# STM32L412CBU6.net
KiCad netlist of a schematic drawn in Altium Designer
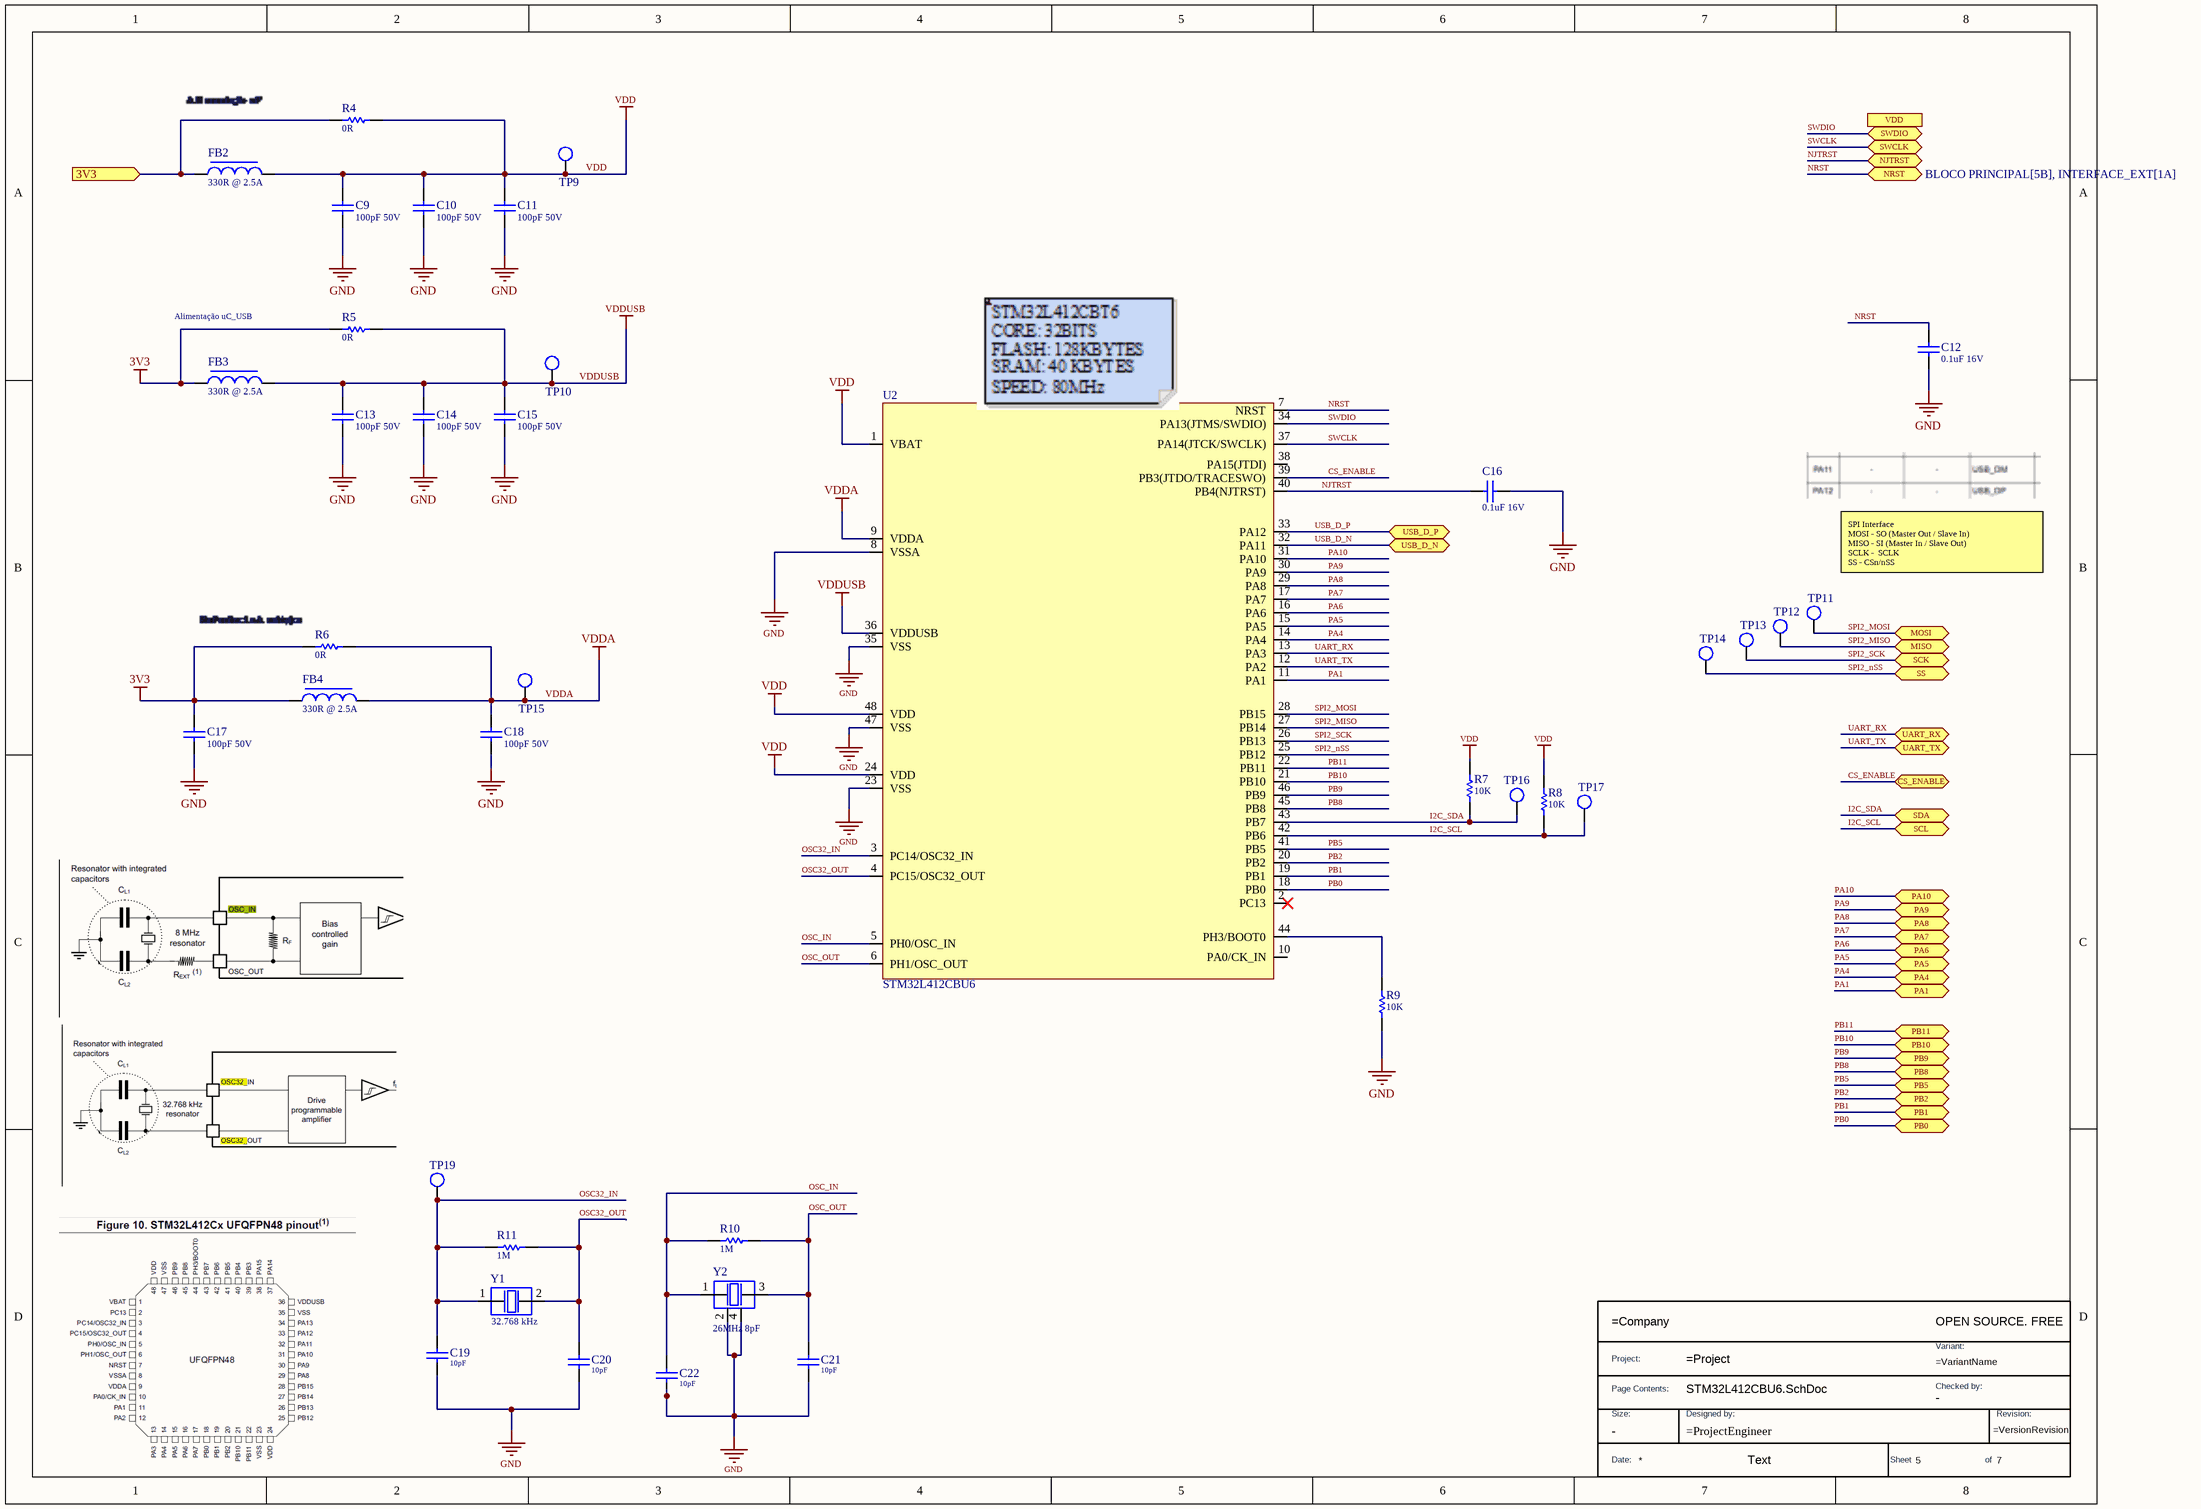
[diagram p0: STM32L412CBU6.SchDoc]

(export (version "E")
  (design (tool "Eeschema 10.0.6"))
  (components
    (comp (ref "C9")
      (value "CC0805JRNPO9BN101")
      (footprint "CAP_0805")
      (description "CAP CER 100PF 50V C0G/NPO 0805")
      (fields (field (name "MANUFACTURER") "YAGEO") (field (name "VALOR") "100pF 50V"))
      (libsource (lib "OBDH_Ed02") (part "CC0805JRNPO9BN101"))
    )
    (comp (ref "C10")
      (value "CC0805JRNPO9BN101")
      (footprint "CAP_0805")
      (description "CAP CER 100PF 50V C0G/NPO 0805")
      (fields (field (name "MANUFACTURER") "YAGEO") (field (name "VALOR") "100pF 50V"))
      (libsource (lib "OBDH_Ed02") (part "CC0805JRNPO9BN101"))
    )
    (comp (ref "C11")
      (value "CC0805JRNPO9BN101")
      (footprint "CAP_0805")
      (description "CAP CER 100PF 50V C0G/NPO 0805")
      (fields (field (name "MANUFACTURER") "YAGEO") (field (name "VALOR") "100pF 50V"))
      (libsource (lib "OBDH_Ed02") (part "CC0805JRNPO9BN101"))
    )
    (comp (ref "C12")
      (value "CL05B104KO5NNNC")
      (footprint "CAP_0805")
      (description "CAP CER 0.1UF 16V X5R 0805")
      (fields (field (name "MANUFACTURER") "Samsung Electro-Mechanics") (field (name "VALOR") "0.1uF 16V"))
      (libsource (lib "OBDH_Ed02") (part "CL05B104KO5NNNC"))
    )
    (comp (ref "C13")
      (value "CC0805JRNPO9BN101")
      (footprint "CAP_0805")
      (description "CAP CER 100PF 50V C0G/NPO 0805")
      (fields (field (name "MANUFACTURER") "YAGEO") (field (name "VALOR") "100pF 50V"))
      (libsource (lib "OBDH_Ed02") (part "CC0805JRNPO9BN101"))
    )
    (comp (ref "C14")
      (value "CC0805JRNPO9BN101")
      (footprint "CAP_0805")
      (description "CAP CER 100PF 50V C0G/NPO 0805")
      (fields (field (name "MANUFACTURER") "YAGEO") (field (name "VALOR") "100pF 50V"))
      (libsource (lib "OBDH_Ed02") (part "CC0805JRNPO9BN101"))
    )
    (comp (ref "C15")
      (value "CC0805JRNPO9BN101")
      (footprint "CAP_0805")
      (description "CAP CER 100PF 50V C0G/NPO 0805")
      (fields (field (name "MANUFACTURER") "YAGEO") (field (name "VALOR") "100pF 50V"))
      (libsource (lib "OBDH_Ed02") (part "CC0805JRNPO9BN101"))
    )
    (comp (ref "C16")
      (value "CL05B104KO5NNNC")
      (footprint "CAP_0805")
      (description "CAP CER 0.1UF 16V X5R 0805")
      (fields (field (name "MANUFACTURER") "Samsung Electro-Mechanics") (field (name "VALOR") "0.1uF 16V"))
      (libsource (lib "OBDH_Ed02") (part "CL05B104KO5NNNC"))
    )
    (comp (ref "C17")
      (value "CC0805JRNPO9BN101")
      (footprint "CAP_0805")
      (description "CAP CER 100PF 50V C0G/NPO 0805")
      (fields (field (name "MANUFACTURER") "YAGEO") (field (name "VALOR") "100pF 50V"))
      (libsource (lib "OBDH_Ed02") (part "CC0805JRNPO9BN101"))
    )
    (comp (ref "C18")
      (value "CC0805JRNPO9BN101")
      (footprint "CAP_0805")
      (description "CAP CER 100PF 50V C0G/NPO 0805")
      (fields (field (name "MANUFACTURER") "YAGEO") (field (name "VALOR") "100pF 50V"))
      (libsource (lib "OBDH_Ed02") (part "CC0805JRNPO9BN101"))
    )
    (comp (ref "C19")
      (value "GRM1555C1H100FA01D")
      (footprint "CAP 0402")
      (description "CAP CER 10PF 50V C0G/NP0 0402")
      (fields (field (name "MANUFACTURER") "Murata Electronics") (field (name "VALOR") "10pF"))
      (libsource (lib "OBDH_Ed02") (part "GRM1555C1H100FA01D"))
    )
    (comp (ref "C20")
      (value "GRM1555C1H100FA01D")
      (footprint "CAP 0402")
      (description "CAP CER 10PF 50V C0G/NP0 0402")
      (fields (field (name "MANUFACTURER") "Murata Electronics") (field (name "VALOR") "10pF"))
      (libsource (lib "OBDH_Ed02") (part "GRM1555C1H100FA01D"))
    )
    (comp (ref "C21")
      (value "GRM1555C1H100FA01D")
      (footprint "CAP 0402")
      (description "CAP CER 10PF 50V C0G/NP0 0402")
      (fields (field (name "MANUFACTURER") "Murata Electronics") (field (name "VALOR") "10pF"))
      (libsource (lib "OBDH_Ed02") (part "GRM1555C1H100FA01D"))
    )
    (comp (ref "C22")
      (value "GRM1555C1H100FA01D")
      (footprint "CAP 0402")
      (description "CAP CER 10PF 50V C0G/NP0 0402")
      (fields (field (name "MANUFACTURER") "Murata Electronics") (field (name "VALOR") "10pF"))
      (libsource (lib "OBDH_Ed02") (part "GRM1555C1H100FA01D"))
    )
    (comp (ref "FB2")
      (value "MPZ2012S331AT000")
      (footprint "IND_0805")
      (description "FERRITE BEAD 330 OHM 0805 1LN")
      (fields (field (name "MANUFACTURER") "TDK Corporation") (field (name "VALOR") "330R @ 2.5A"))
      (libsource (lib "OBDH_Ed02") (part "MPZ2012S331AT000"))
    )
    (comp (ref "FB3")
      (value "MPZ2012S331AT000")
      (footprint "IND_0805")
      (description "FERRITE BEAD 330 OHM 0805 1LN")
      (fields (field (name "MANUFACTURER") "TDK Corporation") (field (name "VALOR") "330R @ 2.5A"))
      (libsource (lib "OBDH_Ed02") (part "MPZ2012S331AT000"))
    )
    (comp (ref "FB4")
      (value "MPZ2012S331AT000")
      (footprint "IND_0805")
      (description "FERRITE BEAD 330 OHM 0805 1LN")
      (fields (field (name "MANUFACTURER") "TDK Corporation") (field (name "VALOR") "330R @ 2.5A"))
      (libsource (lib "OBDH_Ed02") (part "MPZ2012S331AT000"))
    )
    (comp (ref "R4")
      (value "RC0805JR-070RL")
      (footprint "RES_0805")
      (description "RES 0 OHM JUMPER 1/8W 0805")
      (fields (field (name "MANUFACTURER") "YAGEO") (field (name "VALOR") "0R"))
      (libsource (lib "OBDH_Ed02") (part "RC0805JR-070RL"))
    )
    (comp (ref "R5")
      (value "RC0805JR-070RL")
      (footprint "RES_0805")
      (description "RES 0 OHM JUMPER 1/8W 0805")
      (fields (field (name "MANUFACTURER") "YAGEO") (field (name "VALOR") "0R"))
      (libsource (lib "OBDH_Ed02") (part "RC0805JR-070RL"))
    )
    (comp (ref "R6")
      (value "RC0805JR-070RL")
      (footprint "RES_0805")
      (description "RES 0 OHM JUMPER 1/8W 0805")
      (fields (field (name "MANUFACTURER") "YAGEO") (field (name "VALOR") "0R"))
      (libsource (lib "OBDH_Ed02") (part "RC0805JR-070RL"))
    )
    (comp (ref "R7")
      (value "AF0805JR-0710KL")
      (footprint "RES_0805")
      (description "RES SMD 10K OHM 5% 1/8W 0805")
      (fields (field (name "MANUFACTURER") "YAGEO") (field (name "VALOR") "10K"))
      (libsource (lib "OBDH_Ed02") (part "AF0805JR-0710KL"))
    )
    (comp (ref "R8")
      (value "AF0805JR-0710KL")
      (footprint "RES_0805")
      (description "RES SMD 10K OHM 5% 1/8W 0805")
      (fields (field (name "MANUFACTURER") "YAGEO") (field (name "VALOR") "10K"))
      (libsource (lib "OBDH_Ed02") (part "AF0805JR-0710KL"))
    )
    (comp (ref "R9")
      (value "AF0805JR-0710KL")
      (footprint "RES_0805")
      (description "RES SMD 10K OHM 5% 1/8W 0805")
      (fields (field (name "MANUFACTURER") "YAGEO") (field (name "VALOR") "10K"))
      (libsource (lib "OBDH_Ed02") (part "AF0805JR-0710KL"))
    )
    (comp (ref "R10")
      (value "CRCW08051M00JNEA")
      (footprint "RES 0402")
      (description "RES SMD 1M OHM 5% 1/8W 0805")
      (fields (field (name "MANUFACTURER") "Vishay Intertech") (field (name "VALOR") "1M"))
      (libsource (lib "OBDH_Ed02") (part "CRCW08051M00JNEA"))
    )
    (comp (ref "R11")
      (value "CRCW08051M00JNEA")
      (footprint "RES 0402")
      (description "RES SMD 1M OHM 5% 1/8W 0805")
      (fields (field (name "MANUFACTURER") "Vishay Intertech") (field (name "VALOR") "1M"))
      (libsource (lib "OBDH_Ed02") (part "CRCW08051M00JNEA"))
    )
    (comp (ref "TP9")
      (value "TEST_POINT_1.5MM")
      (footprint "TESTPOINT_1.5MM")
      (description "TEST_POINT")
      (libsource (lib "OBDH_Ed02") (part "TEST_POINT_1.5MM"))
    )
    (comp (ref "TP10")
      (value "TEST_POINT_1.5MM")
      (footprint "TESTPOINT_1.5MM")
      (description "TEST_POINT")
      (libsource (lib "OBDH_Ed02") (part "TEST_POINT_1.5MM"))
    )
    (comp (ref "TP11")
      (value "TEST_POINT_1.5MM")
      (footprint "TESTPOINT_1.5MM")
      (description "TEST_POINT")
      (libsource (lib "OBDH_Ed02") (part "TEST_POINT_1.5MM"))
    )
    (comp (ref "TP12")
      (value "TEST_POINT_1.5MM")
      (footprint "TESTPOINT_1.5MM")
      (description "TEST_POINT")
      (libsource (lib "OBDH_Ed02") (part "TEST_POINT_1.5MM"))
    )
    (comp (ref "TP13")
      (value "TEST_POINT_1.5MM")
      (footprint "TESTPOINT_1.5MM")
      (description "TEST_POINT")
      (libsource (lib "OBDH_Ed02") (part "TEST_POINT_1.5MM"))
    )
    (comp (ref "TP14")
      (value "TEST_POINT_1.5MM")
      (footprint "TESTPOINT_1.5MM")
      (description "TEST_POINT")
      (libsource (lib "OBDH_Ed02") (part "TEST_POINT_1.5MM"))
    )
    (comp (ref "TP15")
      (value "TEST_POINT_1.5MM")
      (footprint "TESTPOINT_1.5MM")
      (description "TEST_POINT")
      (libsource (lib "OBDH_Ed02") (part "TEST_POINT_1.5MM"))
    )
    (comp (ref "TP16")
      (value "TEST_POINT_1.5MM")
      (footprint "TESTPOINT_1.5MM")
      (description "TEST_POINT")
      (libsource (lib "OBDH_Ed02") (part "TEST_POINT_1.5MM"))
    )
    (comp (ref "TP17")
      (value "TEST_POINT_1.5MM")
      (footprint "TESTPOINT_1.5MM")
      (description "TEST_POINT")
      (libsource (lib "OBDH_Ed02") (part "TEST_POINT_1.5MM"))
    )
    (comp (ref "TP19")
      (value "TEST_POINT_1.5MM")
      (footprint "TESTPOINT_1.5MM")
      (description "TEST_POINT")
      (libsource (lib "OBDH_Ed02") (part "TEST_POINT_1.5MM"))
    )
    (comp (ref "U2")
      (value "STM32L412CBU6")
      (footprint "QFN-48")
      (libsource (lib "OBDH_Ed02") (part "STM32L412CBU6"))
    )
    (comp (ref "Y1")
      (value "ABS07-32.768KHZ-7-T")
      (footprint "Crystal_32k")
      (description "CRYSTAL 32.7680KHZ 7PF SMD")
      (fields (field (name "MANUFACTURER") "Abracon LLC") (field (name "VALOR") "32.768 kHz"))
      (libsource (lib "OBDH_Ed02") (part "ABS07-32.768KHZ-7-T"))
    )
    (comp (ref "Y2")
      (value "NX3225SA-26MHZ")
      (footprint "Crystal-4SMD")
      (description "CRYSTAL 26.0000MHZ 10PF SMD")
      (fields (field (name "MANUFACTURER") "NDK America, Inc.") (field (name "VALOR") "26MHz 8pF"))
      (libsource (lib "OBDH_Ed02") (part "NX3225SA-26MHZ"))
    )
  )
  (nets
    (net (code "1") (name "/CS_ENABLE") (class "Default")
      (node (ref "U2") (pin "39") (pinfunction "PB3(JTDO/TRACESWO)_39") (pintype "bidirectional"))
    )
    (net (code "2") (name "/I2C_SCL") (class "Default")
      (node (ref "R8") (pin "1") (pinfunction "1_1") (pintype "passive"))
      (node (ref "TP17") (pin "1") (pinfunction "1_1") (pintype "passive"))
      (node (ref "U2") (pin "42") (pinfunction "PB6_42") (pintype "bidirectional"))
    )
    (net (code "3") (name "/I2C_SDA") (class "Default")
      (node (ref "R7") (pin "1") (pinfunction "1_1") (pintype "passive"))
      (node (ref "TP16") (pin "1") (pinfunction "1_1") (pintype "passive"))
      (node (ref "U2") (pin "43") (pinfunction "PB7_43") (pintype "bidirectional"))
    )
    (net (code "4") (name "/NJTRST") (class "Default")
      (node (ref "C16") (pin "1") (pinfunction "1_1") (pintype "passive"))
      (node (ref "U2") (pin "40") (pinfunction "PB4(NJTRST)_40") (pintype "bidirectional"))
    )
    (net (code "5") (name "/NRST") (class "Default")
      (node (ref "C12") (pin "2") (pinfunction "2_2") (pintype "passive"))
      (node (ref "U2") (pin "7") (pinfunction "NRST_7") (pintype "bidirectional"))
    )
    (net (code "6") (name "/OSC32_IN") (class "Default")
      (node (ref "C19") (pin "2") (pinfunction "2_2") (pintype "passive"))
      (node (ref "R11") (pin "1") (pinfunction "1_1") (pintype "passive"))
      (node (ref "TP19") (pin "1") (pinfunction "1_1") (pintype "passive"))
      (node (ref "U2") (pin "3") (pinfunction "PC14/OSC32_IN_3") (pintype "bidirectional"))
      (node (ref "Y1") (pin "1") (pinfunction "1_1") (pintype "passive"))
    )
    (net (code "7") (name "/OSC32_OUT") (class "Default")
      (node (ref "C20") (pin "2") (pinfunction "2_2") (pintype "passive"))
      (node (ref "R11") (pin "2") (pinfunction "2_2") (pintype "passive"))
      (node (ref "U2") (pin "4") (pinfunction "PC15/OSC32_OUT_4") (pintype "bidirectional"))
      (node (ref "Y1") (pin "2") (pinfunction "2_2") (pintype "passive"))
    )
    (net (code "8") (name "/OSC_IN") (class "Default")
      (node (ref "C22") (pin "2") (pinfunction "2_2") (pintype "passive"))
      (node (ref "R10") (pin "1") (pinfunction "1_1") (pintype "passive"))
      (node (ref "U2") (pin "5") (pinfunction "PH0/OSC_IN_5") (pintype "bidirectional"))
      (node (ref "Y2") (pin "1") (pinfunction "1_1") (pintype "passive"))
    )
    (net (code "9") (name "/OSC_OUT") (class "Default")
      (node (ref "C21") (pin "2") (pinfunction "2_2") (pintype "passive"))
      (node (ref "R10") (pin "2") (pinfunction "2_2") (pintype "passive"))
      (node (ref "U2") (pin "6") (pinfunction "PH1/OSC_OUT_6") (pintype "bidirectional"))
      (node (ref "Y2") (pin "3") (pinfunction "3_3") (pintype "passive"))
    )
    (net (code "10") (name "/PA1") (class "Default")
      (node (ref "U2") (pin "11") (pinfunction "PA1_11") (pintype "bidirectional"))
    )
    (net (code "11") (name "/PA4") (class "Default")
      (node (ref "U2") (pin "14") (pinfunction "PA4_14") (pintype "bidirectional"))
    )
    (net (code "12") (name "/PA5") (class "Default")
      (node (ref "U2") (pin "15") (pinfunction "PA5_15") (pintype "bidirectional"))
    )
    (net (code "13") (name "/PA6") (class "Default")
      (node (ref "U2") (pin "16") (pinfunction "PA6_16") (pintype "bidirectional"))
    )
    (net (code "14") (name "/PA7") (class "Default")
      (node (ref "U2") (pin "17") (pinfunction "PA7_17") (pintype "bidirectional"))
    )
    (net (code "15") (name "/PA8") (class "Default")
      (node (ref "U2") (pin "29") (pinfunction "PA8_29") (pintype "bidirectional"))
    )
    (net (code "16") (name "/PA9") (class "Default")
      (node (ref "U2") (pin "30") (pinfunction "PA9_30") (pintype "bidirectional"))
    )
    (net (code "17") (name "/PA10") (class "Default")
      (node (ref "U2") (pin "31") (pinfunction "PA10_31") (pintype "bidirectional"))
    )
    (net (code "18") (name "/PB0") (class "Default")
      (node (ref "U2") (pin "18") (pinfunction "PB0_18") (pintype "bidirectional"))
    )
    (net (code "19") (name "/PB1") (class "Default")
      (node (ref "U2") (pin "19") (pinfunction "PB1_19") (pintype "bidirectional"))
    )
    (net (code "20") (name "/PB2") (class "Default")
      (node (ref "U2") (pin "20") (pinfunction "PB2_20") (pintype "bidirectional"))
    )
    (net (code "21") (name "/PB5") (class "Default")
      (node (ref "U2") (pin "41") (pinfunction "PB5_41") (pintype "bidirectional"))
    )
    (net (code "22") (name "/PB8") (class "Default")
      (node (ref "U2") (pin "45") (pinfunction "PB8_45") (pintype "bidirectional"))
    )
    (net (code "23") (name "/PB9") (class "Default")
      (node (ref "U2") (pin "46") (pinfunction "PB9_46") (pintype "bidirectional"))
    )
    (net (code "24") (name "/PB10") (class "Default")
      (node (ref "U2") (pin "21") (pinfunction "PB10_21") (pintype "bidirectional"))
    )
    (net (code "25") (name "/PB11") (class "Default")
      (node (ref "U2") (pin "22") (pinfunction "PB11_22") (pintype "bidirectional"))
    )
    (net (code "26") (name "/SPI2_MISO") (class "Default")
      (node (ref "TP12") (pin "1") (pinfunction "1_1") (pintype "passive"))
      (node (ref "U2") (pin "27") (pinfunction "PB14_27") (pintype "bidirectional"))
    )
    (net (code "27") (name "/SPI2_MOSI") (class "Default")
      (node (ref "TP11") (pin "1") (pinfunction "1_1") (pintype "passive"))
      (node (ref "U2") (pin "28") (pinfunction "PB15_28") (pintype "bidirectional"))
    )
    (net (code "28") (name "/SPI2_SCK") (class "Default")
      (node (ref "TP13") (pin "1") (pinfunction "1_1") (pintype "passive"))
      (node (ref "U2") (pin "26") (pinfunction "PB13_26") (pintype "bidirectional"))
    )
    (net (code "29") (name "/SPI2_nSS") (class "Default")
      (node (ref "TP14") (pin "1") (pinfunction "1_1") (pintype "passive"))
      (node (ref "U2") (pin "25") (pinfunction "PB12_25") (pintype "bidirectional"))
    )
    (net (code "30") (name "/SWCLK") (class "Default")
      (node (ref "U2") (pin "37") (pinfunction "PA14(JTCK/SWCLK)_37") (pintype "bidirectional"))
    )
    (net (code "31") (name "/SWDIO") (class "Default")
      (node (ref "U2") (pin "34") (pinfunction "PA13(JTMS/SWDIO)_34") (pintype "bidirectional"))
    )
    (net (code "32") (name "/UART_RX") (class "Default")
      (node (ref "U2") (pin "13") (pinfunction "PA3_13") (pintype "bidirectional"))
    )
    (net (code "33") (name "/UART_TX") (class "Default")
      (node (ref "U2") (pin "12") (pinfunction "PA2_12") (pintype "bidirectional"))
    )
    (net (code "34") (name "/USB_D_N") (class "Default")
      (node (ref "U2") (pin "32") (pinfunction "PA11_32") (pintype "bidirectional"))
    )
    (net (code "35") (name "/USB_D_P") (class "Default")
      (node (ref "U2") (pin "33") (pinfunction "PA12_33") (pintype "bidirectional"))
    )
    (net (code "36") (name "3V3") (class "Default")
      (node (ref "C17") (pin "2") (pinfunction "2_2") (pintype "passive"))
      (node (ref "FB2") (pin "1") (pinfunction "1_1") (pintype "passive"))
      (node (ref "FB3") (pin "1") (pinfunction "1_1") (pintype "passive"))
      (node (ref "FB4") (pin "1") (pinfunction "1_1") (pintype "passive"))
      (node (ref "R4") (pin "1") (pinfunction "1_1") (pintype "passive"))
      (node (ref "R5") (pin "1") (pinfunction "1_1") (pintype "passive"))
      (node (ref "R6") (pin "1") (pinfunction "1_1") (pintype "passive"))
    )
    (net (code "37") (name "GND") (class "Default")
      (node (ref "C10") (pin "1") (pinfunction "1_1") (pintype "passive"))
      (node (ref "C11") (pin "1") (pinfunction "1_1") (pintype "passive"))
      (node (ref "C12") (pin "1") (pinfunction "1_1") (pintype "passive"))
      (node (ref "C13") (pin "1") (pinfunction "1_1") (pintype "passive"))
      (node (ref "C14") (pin "1") (pinfunction "1_1") (pintype "passive"))
      (node (ref "C15") (pin "1") (pinfunction "1_1") (pintype "passive"))
      (node (ref "C16") (pin "2") (pinfunction "2_2") (pintype "passive"))
      (node (ref "C17") (pin "1") (pinfunction "1_1") (pintype "passive"))
      (node (ref "C18") (pin "1") (pinfunction "1_1") (pintype "passive"))
      (node (ref "C19") (pin "1") (pinfunction "1_1") (pintype "passive"))
      (node (ref "C20") (pin "1") (pinfunction "1_1") (pintype "passive"))
      (node (ref "C21") (pin "1") (pinfunction "1_1") (pintype "passive"))
      (node (ref "C22") (pin "1") (pinfunction "1_1") (pintype "passive"))
      (node (ref "C9") (pin "1") (pinfunction "1_1") (pintype "passive"))
      (node (ref "R9") (pin "1") (pinfunction "1_1") (pintype "passive"))
      (node (ref "U2") (pin "23") (pinfunction "VSS_23") (pintype "power_in"))
      (node (ref "U2") (pin "35") (pinfunction "VSS_35") (pintype "passive"))
      (node (ref "U2") (pin "47") (pinfunction "VSS_47") (pintype "power_in"))
      (node (ref "U2") (pin "8") (pinfunction "VSSA_8") (pintype "passive"))
      (node (ref "Y2") (pin "2") (pinfunction "2_2") (pintype "passive"))
      (node (ref "Y2") (pin "4") (pinfunction "4_4") (pintype "passive"))
    )
    (net (code "38") (name "Net-(U2-PH3{slash}BOOT0)") (class "Default")
      (node (ref "R9") (pin "2") (pinfunction "2_2") (pintype "passive"))
      (node (ref "U2") (pin "44") (pinfunction "PH3/BOOT0_44") (pintype "bidirectional"))
    )
    (net (code "39") (name "VDD") (class "Default")
      (node (ref "C10") (pin "2") (pinfunction "2_2") (pintype "passive"))
      (node (ref "C11") (pin "2") (pinfunction "2_2") (pintype "passive"))
      (node (ref "C9") (pin "2") (pinfunction "2_2") (pintype "passive"))
      (node (ref "FB2") (pin "2") (pinfunction "2_2") (pintype "passive"))
      (node (ref "R4") (pin "2") (pinfunction "2_2") (pintype "passive"))
      (node (ref "R7") (pin "2") (pinfunction "2_2") (pintype "passive"))
      (node (ref "R8") (pin "2") (pinfunction "2_2") (pintype "passive"))
      (node (ref "TP9") (pin "1") (pinfunction "1_1") (pintype "passive"))
      (node (ref "U2") (pin "1") (pinfunction "VBAT_1") (pintype "power_in"))
      (node (ref "U2") (pin "24") (pinfunction "VDD_24") (pintype "power_in"))
      (node (ref "U2") (pin "48") (pinfunction "VDD_48") (pintype "power_in"))
    )
    (net (code "40") (name "VDDA") (class "Default")
      (node (ref "C18") (pin "2") (pinfunction "2_2") (pintype "passive"))
      (node (ref "FB4") (pin "2") (pinfunction "2_2") (pintype "passive"))
      (node (ref "R6") (pin "2") (pinfunction "2_2") (pintype "passive"))
      (node (ref "TP15") (pin "1") (pinfunction "1_1") (pintype "passive"))
      (node (ref "U2") (pin "9") (pinfunction "VDDA_9") (pintype "power_in"))
    )
    (net (code "41") (name "VDDUSB") (class "Default")
      (node (ref "C13") (pin "2") (pinfunction "2_2") (pintype "passive"))
      (node (ref "C14") (pin "2") (pinfunction "2_2") (pintype "passive"))
      (node (ref "C15") (pin "2") (pinfunction "2_2") (pintype "passive"))
      (node (ref "FB3") (pin "2") (pinfunction "2_2") (pintype "passive"))
      (node (ref "R5") (pin "2") (pinfunction "2_2") (pintype "passive"))
      (node (ref "TP10") (pin "1") (pinfunction "1_1") (pintype "passive"))
      (node (ref "U2") (pin "36") (pinfunction "VDDUSB_36") (pintype "power_in"))
    )
    (net (code "42") (name "unconnected-(U2-PA0{slash}CK_IN-Pad10)") (class "Default")
      (node (ref "U2") (pin "10") (pinfunction "PA0/CK_IN_10") (pintype "bidirectional"))
    )
    (net (code "43") (name "unconnected-(U2-PA15(JTDI)-Pad38)") (class "Default")
      (node (ref "U2") (pin "38") (pinfunction "PA15(JTDI)_38") (pintype "bidirectional"))
    )
    (net (code "44") (name "unconnected-(U2-PC13-Pad2)") (class "Default")
      (node (ref "U2") (pin "2") (pinfunction "PC13_2") (pintype "bidirectional+no_connect"))
    )
  )
)
